# IO.net
KiCad netlist of a schematic drawn in Altium Designer
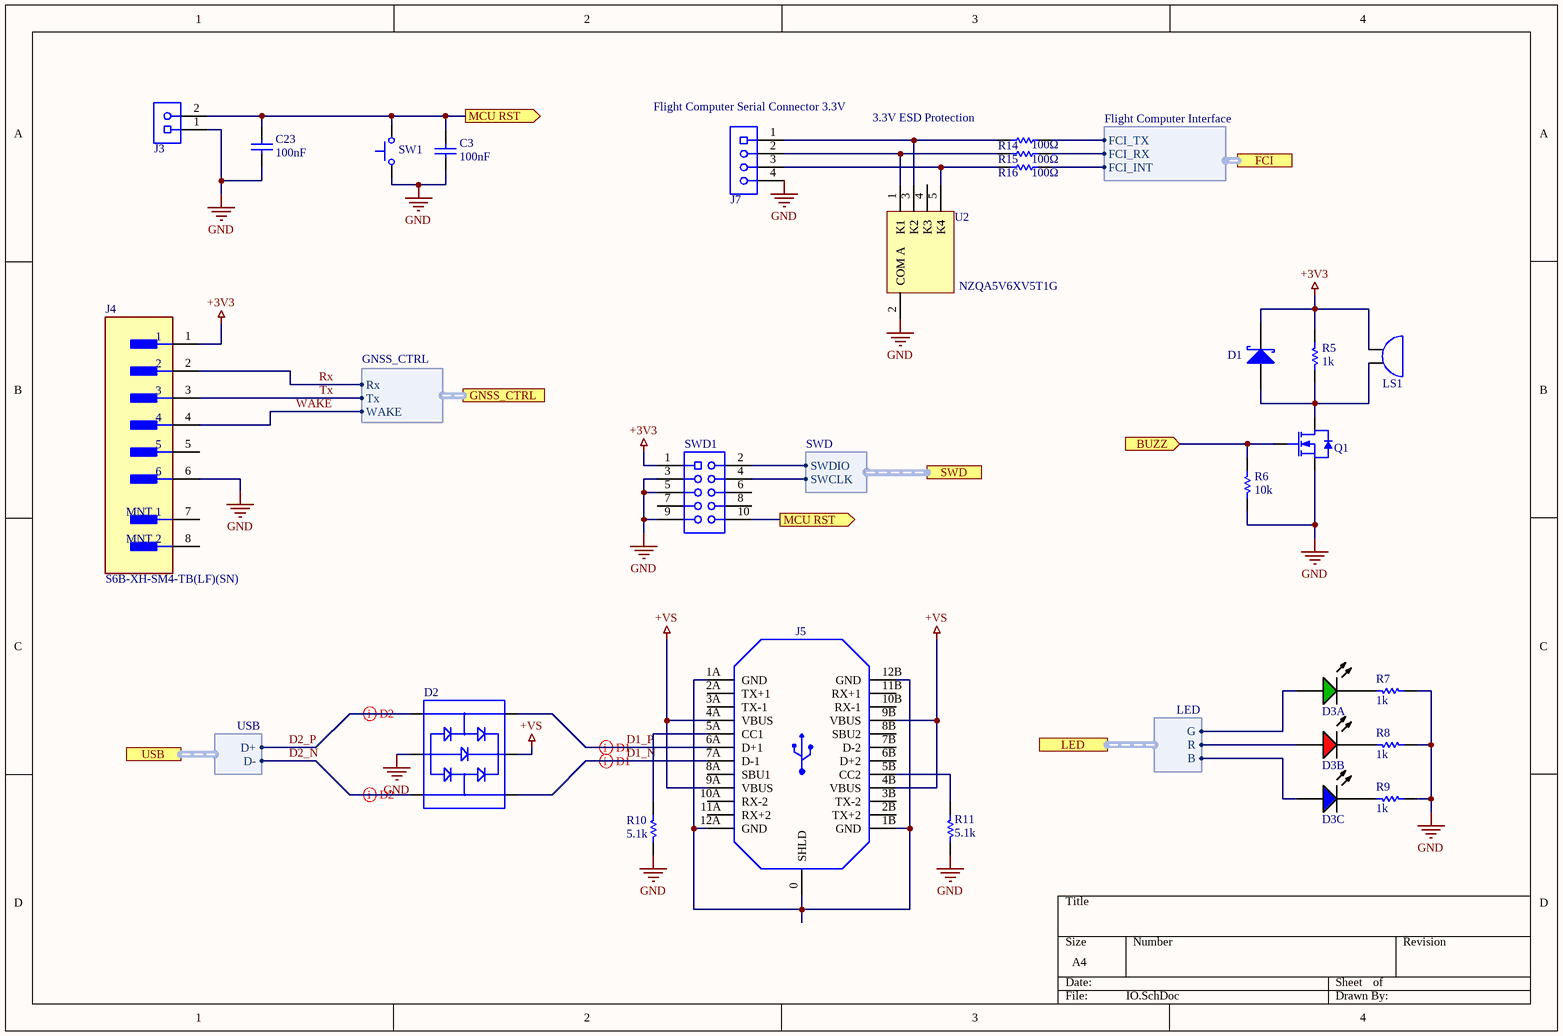
[diagram p0: IO.SchDoc]

(export (version "E")
  (design (tool "Eeschema 10.0.6"))
  (components
    (comp (ref "C3")
      (value "100nF")
      (footprint "CAPC1608X10N")
      (description "Cap Ceramic 0.1uF 50V X7R 20% SMD 0603 125C T/R")
      (fields (field (name "TOLERANCE") "20%") (field (name "Comment") "C0603C104M5RACTU"))
      (libsource (lib "UWA Aerospace") (part "C0603C104M5RACTU"))
    )
    (comp (ref "C23")
      (value "100nF")
      (footprint "CAPC1608X10N")
      (description "Cap Ceramic 0.1uF 50V X7R 20% SMD 0603 125C T/R")
      (fields (field (name "TOLERANCE") "20%") (field (name "Comment") "C0603C104M5RACTU"))
      (libsource (lib "UWA Aerospace") (part "C0603C104M5RACTU"))
    )
    (comp (ref "D1")
      (value "RB521S30T1G")
      (footprint "SODFL160X70-2N")
      (libsource (lib "UWA Aerospace") (part "Diode - Schottky"))
    )
    (comp (ref "D2")
      (value "USBLC6-2SC6")
      (footprint "USBLC6-2SC6-Footprint-1")
      (description "USB ESD Supressor TVS DIODE 5.25V 17V SOT23-6")
      (libsource (lib "UWA Aerospace") (part "Diode - USB Clamp"))
    )
    (comp (ref "D3")
      (value "LRTBGVSR-U4V2-JW+A6BB-D8+S2U2-7Z-20-S")
      (footprint "LRTBGVSG-UEVE-24+AMAQ-29+SCUC-HR-Footprint-1")
      (description "LED Multicolor Red/True Green/Blue 626nm/528nm/465nm 40mA/50mA/50mA 6-Pin SMD T/R")
      (libsource (lib "UWA Aerospace") (part "LRTBGVSG-UEVE-24+AMAQ-29+SCUC-HR"))
    )
    (comp (ref "J3")
      (value "22-28-4020")
      (footprint "22-28-4020-Footprint-1")
      (description "KK 254 Breakaway Header, Vertical, 2 Circuits, Tin (Sn) Plating, Mating Pin Length 6.09mm 2 POS")
      (libsource (lib "UWA Aerospace") (part "22-28-4020"))
    )
    (comp (ref "J4")
      (value "S6B-XH-SM4-TB(LF)(SN)")
      (footprint "FP-S6B-XH-SM4-TB_LF_SN-MFG")
      (description "CONN HEADER SMD R/A 6POS 2.5MM")
      (libsource (lib "Altium Content Vault") (part "ed24c53d9ba001d1a2a686240a95171"))
    )
    (comp (ref "J5")
      (value "SS-52400-003")
      (footprint "SS-52400-003-Footprint-1")
      (description "USB Type-C Receptacle for 1.60mm PCB")
      (libsource (lib "UWA Aerospace") (part "SS-52400-003"))
    )
    (comp (ref "J7")
      (value "53426-0410")
      (footprint "53426-0410-Footprint-1")
      (description "2.50mm Pitch Mini-Lock™ Wire-to-Board Header, Right Angle, Friction and Positive Lock, 4 Circuits")
      (libsource (lib "UWA Aerospace") (part "Connector - 1x4 Single Sided"))
    )
    (comp (ref "LS1")
      (value "CMT-8503-85B-SMT-TR")
      (footprint "CMT-8503-85B-SMT-TR-Footprint-1")
      (description "8.5 mm, 3.6 Vo-p, 85 dB, Surface Mount (SMT), Magnetic Audio Transducer Buzzer")
      (libsource (lib "UWA Aerospace") (part "Buzzer"))
    )
    (comp (ref "Q1")
      (value "2N7002NXAKR")
      (footprint "SOT95P230X110-3N")
      (description "2N7002NXAK - 60 V, single N-channel Trench MOSFET")
      (libsource (lib "UWA Aerospace") (part "2N7002NXAKR"))
    )
    (comp (ref "R5")
      (value "1k")
      (footprint "RESC1608X06N")
      (fields (field (name "TOLERANCE") "1%") (field (name "Comment") "CRCW06031K00FKEA"))
      (libsource (lib "UWA Aerospace") (part "CRCW06031K00FKEAC"))
    )
    (comp (ref "R6")
      (value "10k")
      (footprint "RESC1608X06N")
      (fields (field (name "TOLERANCE") "1%") (field (name "Comment") "CRCW060310K0FKEA"))
      (libsource (lib "UWA Aerospace") (part "CRCW060310K0FKEA"))
    )
    (comp (ref "R7")
      (value "1k")
      (footprint "RESC1608X06N")
      (fields (field (name "TOLERANCE") "1%") (field (name "Comment") "CRCW06031K00FKEA"))
      (libsource (lib "UWA Aerospace") (part "CRCW06031K00FKEAC"))
    )
    (comp (ref "R8")
      (value "1k")
      (footprint "RESC1608X06N")
      (fields (field (name "TOLERANCE") "1%") (field (name "Comment") "CRCW06031K00FKEA"))
      (libsource (lib "UWA Aerospace") (part "CRCW06031K00FKEAC"))
    )
    (comp (ref "R9")
      (value "1k")
      (footprint "RESC1608X06N")
      (fields (field (name "TOLERANCE") "1%") (field (name "Comment") "CRCW06031K00FKEA"))
      (libsource (lib "UWA Aerospace") (part "CRCW06031K00FKEAC"))
    )
    (comp (ref "R10")
      (value "5.1k")
      (footprint "RESC1608X06N")
      (description "Res Thick Film 0603 5.1K Ohm 1% 1/10W ±100ppm/°C Molded SMD SMD Paper T/R")
      (fields (field (name "TOLERANCE") "1%") (field (name "Comment") "CRCW06035K10FKEA"))
      (libsource (lib "UWA Aerospace") (part "Resistor"))
    )
    (comp (ref "R11")
      (value "5.1k")
      (footprint "RESC1608X06N")
      (description "Res Thick Film 0603 5.1K Ohm 1% 1/10W ±100ppm/°C Molded SMD SMD Paper T/R")
      (fields (field (name "TOLERANCE") "1%") (field (name "Comment") "CRCW06035K10FKEA"))
      (libsource (lib "UWA Aerospace") (part "Resistor"))
    )
    (comp (ref "R14")
      (value "100Ω")
      (footprint "RESC1609X50X30ML8T20")
      (description "Chip Resistor, 100 Ohm, +/- 1%, 100 mW,-55 to 155 degC, 0603 (1608 Metric), RoHS, Tape and Ree")
      (fields (field (name "MANUFACTURER") "Vishay Semiconductor"))
      (libsource (lib "Altium Content Vault") (part "RES-2"))
    )
    (comp (ref "R15")
      (value "100Ω")
      (footprint "RESC1609X50X30ML8T20")
      (description "Chip Resistor, 100 Ohm, +/- 1%, 100 mW,-55 to 155 degC, 0603 (1608 Metric), RoHS, Tape and Ree")
      (fields (field (name "MANUFACTURER") "Vishay Semiconductor"))
      (libsource (lib "Altium Content Vault") (part "RES-2"))
    )
    (comp (ref "R16")
      (value "100Ω")
      (footprint "RESC1609X50X30ML8T20")
      (description "Chip Resistor, 100 Ohm, +/- 1%, 100 mW,-55 to 155 degC, 0603 (1608 Metric), RoHS, Tape and Ree")
      (fields (field (name "MANUFACTURER") "Vishay Semiconductor"))
      (libsource (lib "Altium Content Vault") (part "RES-2"))
    )
    (comp (ref "SW1")
      (value "B3U-1000P")
      (footprint "OMRON-B3U-1000_V")
      (description "SWITCH TACTILE SPST-NO 0.05A 12V")
      (libsource (lib "UWA Aerospace") (part "B3U-1000P"))
    )
    (comp (ref "SWD1")
      (value "M22-2520505")
      (footprint "M22-2520505-Footprint-1")
      (description "CONN HEADER 2MM VERT AU 10POS")
      (libsource (lib "UWA Aerospace") (part "M22-2520505"))
    )
    (comp (ref "U2")
      (value "NZQA5V6XV5T1G")
      (footprint "ONSC-SOT-553-5-463B_B_V")
      (description "Quad Array for ESD Protection, 5-Pin SOT-553, Pb-Free, Tape and Reel")
      (fields (field (name "MANUFACTURER") "On Semiconductor"))
      (libsource (lib "Altium Content Vault") (part "ONSC-NZQAXVX-SOT-553-5-463B"))
    )
  )
  (nets
    (net (code "8") (name "+3V3") (class "Default")
      (node (ref "D1") (pin "1") (pinfunction "K_1") (pintype "passive"))
      (node (ref "J4") (pin "1") (pinfunction "1_1") (pintype "passive"))
      (node (ref "LS1") (pin "1") (pinfunction "1_1") (pintype "passive"))
      (node (ref "R5") (pin "2") (pinfunction "2_2") (pintype "passive"))
      (node (ref "SWD1") (pin "1") (pinfunction "VDD_1") (pintype "passive"))
    )
    (net (code "9") (name "+VS") (class "Default")
      (node (ref "D2") (pin "5") (pinfunction "5_5") (pintype "passive"))
      (node (ref "J5") (pin "4A") (pinfunction "VBUS_4A") (pintype "passive"))
      (node (ref "J5") (pin "4B") (pinfunction "VBUS_4B") (pintype "passive"))
      (node (ref "J5") (pin "9A") (pinfunction "VBUS_9A") (pintype "passive"))
      (node (ref "J5") (pin "9B") (pinfunction "VBUS_9B") (pintype "passive"))
    )
    (net (code "10") (name "/B") (class "Default")
      (node (ref "D3") (pin "2") (pinfunction "A3_2") (pintype "passive"))
    )
    (net (code "11") (name "/BUZZ") (class "Default")
      (node (ref "Q1") (pin "1") (pinfunction "G_1") (pintype "passive"))
      (node (ref "R6") (pin "2") (pinfunction "2_2") (pintype "passive"))
    )
    (net (code "12") (name "/D1_N") (class "Default")
      (node (ref "D2") (pin "6") (pinfunction "6_6") (pintype "passive"))
      (node (ref "J5") (pin "7A") (pinfunction "D-1_7A") (pintype "passive"))
    )
    (net (code "13") (name "/D1_P") (class "Default")
      (node (ref "D2") (pin "4") (pinfunction "4_4") (pintype "passive"))
      (node (ref "J5") (pin "6A") (pinfunction "D+1_6A") (pintype "passive"))
    )
    (net (code "14") (name "/D2_N") (class "Default")
      (node (ref "D2") (pin "1") (pinfunction "1_1") (pintype "passive"))
    )
    (net (code "15") (name "/D2_P") (class "Default")
      (node (ref "D2") (pin "3") (pinfunction "3_3") (pintype "passive"))
    )
    (net (code "16") (name "/FCI_INT") (class "Default")
      (node (ref "R16") (pin "1") (pinfunction "1_1") (pintype "passive"))
    )
    (net (code "17") (name "/FCI_RX") (class "Default")
      (node (ref "R15") (pin "1") (pinfunction "1_1") (pintype "passive"))
    )
    (net (code "18") (name "/FCI_TX") (class "Default")
      (node (ref "R14") (pin "1") (pinfunction "1_1") (pintype "passive"))
    )
    (net (code "19") (name "/G") (class "Default")
      (node (ref "D3") (pin "6") (pinfunction "A1_6") (pintype "passive"))
    )
    (net (code "20") (name "/MCU RST") (class "Default")
      (node (ref "C23") (pin "2") (pinfunction "2_2") (pintype "passive"))
      (node (ref "C3") (pin "2") (pinfunction "2_2") (pintype "passive"))
      (node (ref "J3") (pin "2") (pinfunction "2_2") (pintype "passive"))
      (node (ref "SW1") (pin "1") (pinfunction "1_1") (pintype "passive"))
      (node (ref "SWD1") (pin "10") (pinfunction "NRST_10") (pintype "passive"))
    )
    (net (code "21") (name "/R") (class "Default")
      (node (ref "D3") (pin "5") (pinfunction "A2_5") (pintype "passive"))
    )
    (net (code "22") (name "/Rx") (class "Default")
      (node (ref "J4") (pin "2") (pinfunction "2_2") (pintype "passive"))
    )
    (net (code "23") (name "/SWCLK") (class "Default")
      (node (ref "SWD1") (pin "4") (pinfunction "SWCLK_4") (pintype "passive"))
    )
    (net (code "24") (name "/SWDIO") (class "Default")
      (node (ref "SWD1") (pin "2") (pinfunction "SWDIO_2") (pintype "passive"))
    )
    (net (code "25") (name "/Tx") (class "Default")
      (node (ref "J4") (pin "3") (pinfunction "3_3") (pintype "passive"))
    )
    (net (code "26") (name "/WAKE") (class "Default")
      (node (ref "J4") (pin "4") (pinfunction "4_4") (pintype "passive"))
    )
    (net (code "32") (name "GND") (class "Default")
      (node (ref "C23") (pin "1") (pinfunction "1_1") (pintype "passive"))
      (node (ref "C3") (pin "1") (pinfunction "1_1") (pintype "passive"))
      (node (ref "D2") (pin "2") (pinfunction "2_2") (pintype "passive"))
      (node (ref "J3") (pin "1") (pinfunction "1_1") (pintype "passive"))
      (node (ref "J4") (pin "6") (pinfunction "6_6") (pintype "passive"))
      (node (ref "J7") (pin "4") (pinfunction "4_4") (pintype "passive"))
      (node (ref "Q1") (pin "2") (pinfunction "S_2") (pintype "passive"))
      (node (ref "R10") (pin "1") (pinfunction "1_1") (pintype "passive"))
      (node (ref "R11") (pin "1") (pinfunction "1_1") (pintype "passive"))
      (node (ref "R6") (pin "1") (pinfunction "1_1") (pintype "passive"))
      (node (ref "R7") (pin "2") (pinfunction "2_2") (pintype "passive"))
      (node (ref "R8") (pin "2") (pinfunction "2_2") (pintype "passive"))
      (node (ref "R9") (pin "2") (pinfunction "2_2") (pintype "passive"))
      (node (ref "SW1") (pin "2") (pinfunction "2_2") (pintype "passive"))
      (node (ref "SWD1") (pin "3") (pinfunction "GND_3") (pintype "passive"))
      (node (ref "SWD1") (pin "5") (pinfunction "GND_5") (pintype "passive"))
      (node (ref "SWD1") (pin "9") (pinfunction "GND_9") (pintype "passive"))
      (node (ref "U2") (pin "2") (pinfunction "COM_A_2") (pintype "passive"))
    )
    (net (code "33") (name "Net-(D1-A)") (class "Default")
      (node (ref "D1") (pin "2") (pinfunction "A_2") (pintype "passive"))
      (node (ref "LS1") (pin "2") (pinfunction "2_2") (pintype "passive"))
      (node (ref "Q1") (pin "3") (pinfunction "D_3") (pintype "passive"))
      (node (ref "R5") (pin "1") (pinfunction "1_1") (pintype "passive"))
    )
    (net (code "34") (name "Net-(D3A-K1)") (class "Default")
      (node (ref "D3") (pin "1") (pinfunction "K1_1") (pintype "passive"))
      (node (ref "R7") (pin "1") (pinfunction "1_1") (pintype "passive"))
    )
    (net (code "35") (name "Net-(D3B-K2)") (class "Default")
      (node (ref "D3") (pin "4") (pinfunction "K2_4") (pintype "passive"))
      (node (ref "R8") (pin "1") (pinfunction "1_1") (pintype "passive"))
    )
    (net (code "36") (name "Net-(D3C-K3)") (class "Default")
      (node (ref "D3") (pin "3") (pinfunction "K3_3") (pintype "passive"))
      (node (ref "R9") (pin "1") (pinfunction "1_1") (pintype "passive"))
    )
    (net (code "37") (name "Net-(J5-CC1)") (class "Default")
      (node (ref "J5") (pin "5A") (pinfunction "CC1_5A") (pintype "passive"))
      (node (ref "R10") (pin "2") (pinfunction "2_2") (pintype "passive"))
    )
    (net (code "38") (name "Net-(J5-CC2)") (class "Default")
      (node (ref "J5") (pin "5B") (pinfunction "CC2_5B") (pintype "passive"))
      (node (ref "R11") (pin "2") (pinfunction "2_2") (pintype "passive"))
    )
    (net (code "39") (name "Net-(J5-SHLD)") (class "Default")
      (node (ref "J5") (pin "0") (pinfunction "SHLD_0") (pintype "passive"))
      (node (ref "J5") (pin "12A") (pinfunction "GND_12A") (pintype "passive"))
      (node (ref "J5") (pin "12B") (pinfunction "GND_12B") (pintype "passive"))
      (node (ref "J5") (pin "1A") (pinfunction "GND_1A") (pintype "passive"))
      (node (ref "J5") (pin "1B") (pinfunction "GND_1B") (pintype "passive"))
    )
    (net (code "40") (name "Net-(U2-K1)") (class "Default")
      (node (ref "J7") (pin "2") (pinfunction "2_2") (pintype "passive"))
      (node (ref "R15") (pin "2") (pinfunction "2_2") (pintype "passive"))
      (node (ref "U2") (pin "1") (pinfunction "K1_1") (pintype "passive"))
    )
    (net (code "41") (name "Net-(U2-K2)") (class "Default")
      (node (ref "J7") (pin "1") (pinfunction "1_1") (pintype "passive"))
      (node (ref "R14") (pin "2") (pinfunction "2_2") (pintype "passive"))
      (node (ref "U2") (pin "3") (pinfunction "K2_3") (pintype "passive"))
    )
    (net (code "42") (name "Net-(U2-K4)") (class "Default")
      (node (ref "J7") (pin "3") (pinfunction "3_3") (pintype "passive"))
      (node (ref "R16") (pin "2") (pinfunction "2_2") (pintype "passive"))
      (node (ref "U2") (pin "5") (pinfunction "K4_5") (pintype "passive"))
    )
    (net (code "43") (name "unconnected-(J4-MNT_1-Pad7)") (class "Default")
      (node (ref "J4") (pin "7") (pinfunction "MNT_1_7") (pintype "passive"))
    )
    (net (code "44") (name "unconnected-(J4-MNT_2-Pad8)") (class "Default")
      (node (ref "J4") (pin "8") (pinfunction "MNT_2_8") (pintype "passive"))
    )
    (net (code "45") (name "unconnected-(J4-Pad5)") (class "Default")
      (node (ref "J4") (pin "5") (pinfunction "5_5") (pintype "passive"))
    )
    (net (code "46") (name "unconnected-(J5-D+2-Pad6B)") (class "Default")
      (node (ref "J5") (pin "6B") (pinfunction "D+2_6B") (pintype "passive"))
    )
    (net (code "47") (name "unconnected-(J5-D-2-Pad7B)") (class "Default")
      (node (ref "J5") (pin "7B") (pinfunction "D-2_7B") (pintype "passive"))
    )
    (net (code "48") (name "unconnected-(J5-RX+1-Pad11B)") (class "Default")
      (node (ref "J5") (pin "11B") (pinfunction "RX+1_11B") (pintype "passive"))
    )
    (net (code "49") (name "unconnected-(J5-RX+2-Pad11A)") (class "Default")
      (node (ref "J5") (pin "11A") (pinfunction "RX+2_11A") (pintype "passive"))
    )
    (net (code "50") (name "unconnected-(J5-RX-1-Pad10B)") (class "Default")
      (node (ref "J5") (pin "10B") (pinfunction "RX-1_10B") (pintype "passive"))
    )
    (net (code "51") (name "unconnected-(J5-RX-2-Pad10A)") (class "Default")
      (node (ref "J5") (pin "10A") (pinfunction "RX-2_10A") (pintype "passive"))
    )
    (net (code "52") (name "unconnected-(J5-SBU1-Pad8A)") (class "Default")
      (node (ref "J5") (pin "8A") (pinfunction "SBU1_8A") (pintype "passive"))
    )
    (net (code "53") (name "unconnected-(J5-SBU2-Pad8B)") (class "Default")
      (node (ref "J5") (pin "8B") (pinfunction "SBU2_8B") (pintype "passive"))
    )
    (net (code "54") (name "unconnected-(J5-TX+1-Pad2A)") (class "Default")
      (node (ref "J5") (pin "2A") (pinfunction "TX+1_2A") (pintype "passive"))
    )
    (net (code "55") (name "unconnected-(J5-TX+2-Pad2B)") (class "Default")
      (node (ref "J5") (pin "2B") (pinfunction "TX+2_2B") (pintype "passive"))
    )
    (net (code "56") (name "unconnected-(J5-TX-1-Pad3A)") (class "Default")
      (node (ref "J5") (pin "3A") (pinfunction "TX-1_3A") (pintype "passive"))
    )
    (net (code "57") (name "unconnected-(J5-TX-2-Pad3B)") (class "Default")
      (node (ref "J5") (pin "3B") (pinfunction "TX-2_3B") (pintype "passive"))
    )
    (net (code "58") (name "unconnected-(SWD1-NC-Pad7)") (class "Default")
      (node (ref "SWD1") (pin "7") (pinfunction "NC_7") (pintype "passive"))
    )
    (net (code "59") (name "unconnected-(SWD1-NC-Pad8)") (class "Default")
      (node (ref "SWD1") (pin "8") (pinfunction "NC_8") (pintype "passive"))
    )
    (net (code "60") (name "unconnected-(SWD1-SWO-Pad6)") (class "Default")
      (node (ref "SWD1") (pin "6") (pinfunction "SWO_6") (pintype "passive"))
    )
    (net (code "61") (name "unconnected-(U2-K3-Pad4)") (class "Default")
      (node (ref "U2") (pin "4") (pinfunction "K3_4") (pintype "passive"))
    )
  )
)
